# hp16555_adapter.net
KiCad netlist of a schematic drawn in EAGLE
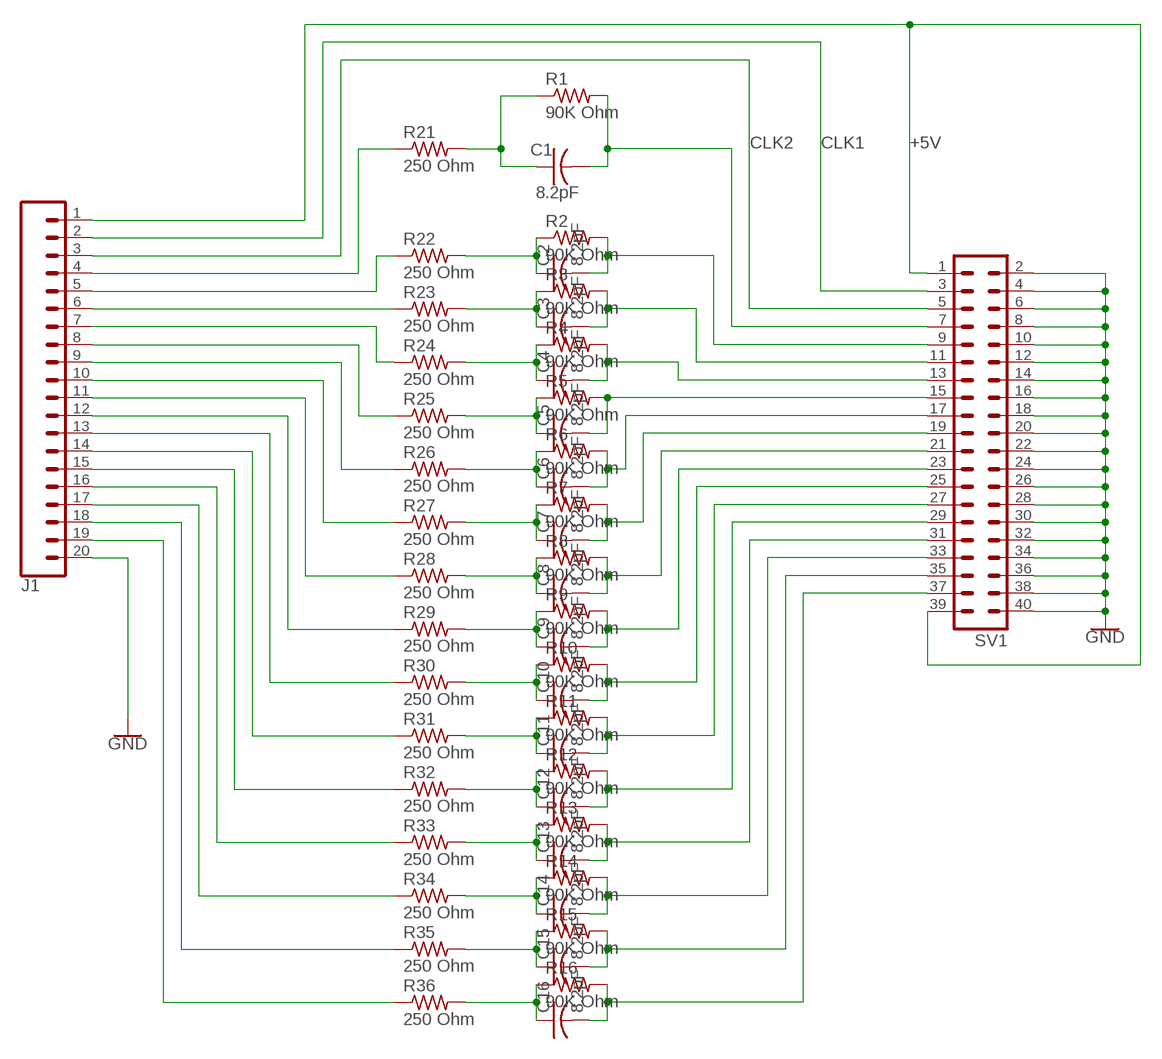
[diagram p0: schematic, sheet 1]

(export (version "E")
  (design (tool "Eeschema 10.0.6"))
  (components
    (comp (ref "C1")
      (value "8.2pF")
      (footprint "eagle-import:C1206")
      (libsource (lib "eagle-import") (part "C-USC1206"))
    )
    (comp (ref "C2")
      (value "8.2pF")
      (footprint "eagle-import:C1206")
      (libsource (lib "eagle-import") (part "C-USC1206"))
    )
    (comp (ref "C3")
      (value "8.2pF")
      (footprint "eagle-import:C1206")
      (libsource (lib "eagle-import") (part "C-USC1206"))
    )
    (comp (ref "C4")
      (value "8.2pF")
      (footprint "eagle-import:C1206")
      (libsource (lib "eagle-import") (part "C-USC1206"))
    )
    (comp (ref "C5")
      (value "8.2pF")
      (footprint "eagle-import:C1206")
      (libsource (lib "eagle-import") (part "C-USC1206"))
    )
    (comp (ref "C6")
      (value "8.2pF")
      (footprint "eagle-import:C1206")
      (libsource (lib "eagle-import") (part "C-USC1206"))
    )
    (comp (ref "C7")
      (value "8.2pF")
      (footprint "eagle-import:C1206")
      (libsource (lib "eagle-import") (part "C-USC1206"))
    )
    (comp (ref "C8")
      (value "8.2pF")
      (footprint "eagle-import:C1206")
      (libsource (lib "eagle-import") (part "C-USC1206"))
    )
    (comp (ref "C9")
      (value "8.2pF")
      (footprint "eagle-import:C1206")
      (libsource (lib "eagle-import") (part "C-USC1206"))
    )
    (comp (ref "C10")
      (value "8.2pF")
      (footprint "eagle-import:C1206")
      (libsource (lib "eagle-import") (part "C-USC1206"))
    )
    (comp (ref "C11")
      (value "8.2pF")
      (footprint "eagle-import:C1206")
      (libsource (lib "eagle-import") (part "C-USC1206"))
    )
    (comp (ref "C12")
      (value "8.2pF")
      (footprint "eagle-import:C1206")
      (libsource (lib "eagle-import") (part "C-USC1206"))
    )
    (comp (ref "C13")
      (value "8.2pF")
      (footprint "eagle-import:C1206")
      (libsource (lib "eagle-import") (part "C-USC1206"))
    )
    (comp (ref "C14")
      (value "8.2pF")
      (footprint "eagle-import:C1206")
      (libsource (lib "eagle-import") (part "C-USC1206"))
    )
    (comp (ref "C15")
      (value "8.2pF")
      (footprint "eagle-import:C1206")
      (libsource (lib "eagle-import") (part "C-USC1206"))
    )
    (comp (ref "C16")
      (value "8.2pF")
      (footprint "eagle-import:C1206")
      (libsource (lib "eagle-import") (part "C-USC1206"))
    )
    (comp (ref "J1")
      (value "CONN_20")
      (footprint "eagle-import:1X20")
      (libsource (lib "eagle-import") (part "CONN_20"))
    )
    (comp (ref "R1")
      (value "90K Ohm")
      (footprint "eagle-import:M1206")
      (libsource (lib "eagle-import") (part "R-US_M1206"))
    )
    (comp (ref "R2")
      (value "90K Ohm")
      (footprint "eagle-import:M1206")
      (libsource (lib "eagle-import") (part "R-US_M1206"))
    )
    (comp (ref "R3")
      (value "90K Ohm")
      (footprint "eagle-import:M1206")
      (libsource (lib "eagle-import") (part "R-US_M1206"))
    )
    (comp (ref "R4")
      (value "90K Ohm")
      (footprint "eagle-import:M1206")
      (libsource (lib "eagle-import") (part "R-US_M1206"))
    )
    (comp (ref "R5")
      (value "90K Ohm")
      (footprint "eagle-import:M1206")
      (libsource (lib "eagle-import") (part "R-US_M1206"))
    )
    (comp (ref "R6")
      (value "90K Ohm")
      (footprint "eagle-import:M1206")
      (libsource (lib "eagle-import") (part "R-US_M1206"))
    )
    (comp (ref "R7")
      (value "90K Ohm")
      (footprint "eagle-import:M1206")
      (libsource (lib "eagle-import") (part "R-US_M1206"))
    )
    (comp (ref "R8")
      (value "90K Ohm")
      (footprint "eagle-import:M1206")
      (libsource (lib "eagle-import") (part "R-US_M1206"))
    )
    (comp (ref "R9")
      (value "90K Ohm")
      (footprint "eagle-import:M1206")
      (libsource (lib "eagle-import") (part "R-US_M1206"))
    )
    (comp (ref "R10")
      (value "90K Ohm")
      (footprint "eagle-import:M1206")
      (libsource (lib "eagle-import") (part "R-US_M1206"))
    )
    (comp (ref "R11")
      (value "90K Ohm")
      (footprint "eagle-import:M1206")
      (libsource (lib "eagle-import") (part "R-US_M1206"))
    )
    (comp (ref "R12")
      (value "90K Ohm")
      (footprint "eagle-import:M1206")
      (libsource (lib "eagle-import") (part "R-US_M1206"))
    )
    (comp (ref "R13")
      (value "90K Ohm")
      (footprint "eagle-import:M1206")
      (libsource (lib "eagle-import") (part "R-US_M1206"))
    )
    (comp (ref "R14")
      (value "90K Ohm")
      (footprint "eagle-import:M1206")
      (libsource (lib "eagle-import") (part "R-US_M1206"))
    )
    (comp (ref "R15")
      (value "90K Ohm")
      (footprint "eagle-import:M1206")
      (libsource (lib "eagle-import") (part "R-US_M1206"))
    )
    (comp (ref "R16")
      (value "90K Ohm")
      (footprint "eagle-import:M1206")
      (libsource (lib "eagle-import") (part "R-US_M1206"))
    )
    (comp (ref "R21")
      (value "250 Ohm")
      (footprint "eagle-import:M1206")
      (libsource (lib "eagle-import") (part "R-US_M1206"))
    )
    (comp (ref "R22")
      (value "250 Ohm")
      (footprint "eagle-import:M1206")
      (libsource (lib "eagle-import") (part "R-US_M1206"))
    )
    (comp (ref "R23")
      (value "250 Ohm")
      (footprint "eagle-import:M1206")
      (libsource (lib "eagle-import") (part "R-US_M1206"))
    )
    (comp (ref "R24")
      (value "250 Ohm")
      (footprint "eagle-import:M1206")
      (libsource (lib "eagle-import") (part "R-US_M1206"))
    )
    (comp (ref "R25")
      (value "250 Ohm")
      (footprint "eagle-import:M1206")
      (libsource (lib "eagle-import") (part "R-US_M1206"))
    )
    (comp (ref "R26")
      (value "250 Ohm")
      (footprint "eagle-import:M1206")
      (libsource (lib "eagle-import") (part "R-US_M1206"))
    )
    (comp (ref "R27")
      (value "250 Ohm")
      (footprint "eagle-import:M1206")
      (libsource (lib "eagle-import") (part "R-US_M1206"))
    )
    (comp (ref "R28")
      (value "250 Ohm")
      (footprint "eagle-import:M1206")
      (libsource (lib "eagle-import") (part "R-US_M1206"))
    )
    (comp (ref "R29")
      (value "250 Ohm")
      (footprint "eagle-import:M1206")
      (libsource (lib "eagle-import") (part "R-US_M1206"))
    )
    (comp (ref "R30")
      (value "250 Ohm")
      (footprint "eagle-import:M1206")
      (libsource (lib "eagle-import") (part "R-US_M1206"))
    )
    (comp (ref "R31")
      (value "250 Ohm")
      (footprint "eagle-import:M1206")
      (libsource (lib "eagle-import") (part "R-US_M1206"))
    )
    (comp (ref "R32")
      (value "250 Ohm")
      (footprint "eagle-import:M1206")
      (libsource (lib "eagle-import") (part "R-US_M1206"))
    )
    (comp (ref "R33")
      (value "250 Ohm")
      (footprint "eagle-import:M1206")
      (libsource (lib "eagle-import") (part "R-US_M1206"))
    )
    (comp (ref "R34")
      (value "250 Ohm")
      (footprint "eagle-import:M1206")
      (libsource (lib "eagle-import") (part "R-US_M1206"))
    )
    (comp (ref "R35")
      (value "250 Ohm")
      (footprint "eagle-import:M1206")
      (libsource (lib "eagle-import") (part "R-US_M1206"))
    )
    (comp (ref "R36")
      (value "250 Ohm")
      (footprint "eagle-import:M1206")
      (libsource (lib "eagle-import") (part "R-US_M1206"))
    )
    (comp (ref "SV1")
      (value "MA20-2")
      (footprint "eagle-import:MA20-2")
      (libsource (lib "eagle-import") (part "MA20-2"))
    )
  )
  (nets
    (net (code "1") (name "/+5V") (class "Default")
      (node (ref "J1") (pin "1") (pinfunction "1_1") (pintype "passive"))
      (node (ref "SV1") (pin "1") (pinfunction "1_1") (pintype "passive"))
      (node (ref "SV1") (pin "39") (pinfunction "39_39") (pintype "passive"))
    )
    (net (code "2") (name "/CLK1") (class "Default")
      (node (ref "J1") (pin "2") (pinfunction "2_2") (pintype "passive"))
      (node (ref "SV1") (pin "3") (pinfunction "3_3") (pintype "passive"))
    )
    (net (code "3") (name "/CLK2") (class "Default")
      (node (ref "J1") (pin "3") (pinfunction "3_3") (pintype "passive"))
      (node (ref "SV1") (pin "5") (pinfunction "5_5") (pintype "passive"))
    )
    (net (code "4") (name "GND") (class "Default")
      (node (ref "J1") (pin "20") (pinfunction "20_20") (pintype "passive"))
      (node (ref "SV1") (pin "10") (pinfunction "10_10") (pintype "passive"))
      (node (ref "SV1") (pin "12") (pinfunction "12_12") (pintype "passive"))
      (node (ref "SV1") (pin "14") (pinfunction "14_14") (pintype "passive"))
      (node (ref "SV1") (pin "16") (pinfunction "16_16") (pintype "passive"))
      (node (ref "SV1") (pin "18") (pinfunction "18_18") (pintype "passive"))
      (node (ref "SV1") (pin "2") (pinfunction "2_2") (pintype "passive"))
      (node (ref "SV1") (pin "20") (pinfunction "20_20") (pintype "passive"))
      (node (ref "SV1") (pin "22") (pinfunction "22_22") (pintype "passive"))
      (node (ref "SV1") (pin "24") (pinfunction "24_24") (pintype "passive"))
      (node (ref "SV1") (pin "26") (pinfunction "26_26") (pintype "passive"))
      (node (ref "SV1") (pin "28") (pinfunction "28_28") (pintype "passive"))
      (node (ref "SV1") (pin "30") (pinfunction "30_30") (pintype "passive"))
      (node (ref "SV1") (pin "32") (pinfunction "32_32") (pintype "passive"))
      (node (ref "SV1") (pin "34") (pinfunction "34_34") (pintype "passive"))
      (node (ref "SV1") (pin "36") (pinfunction "36_36") (pintype "passive"))
      (node (ref "SV1") (pin "38") (pinfunction "38_38") (pintype "passive"))
      (node (ref "SV1") (pin "4") (pinfunction "4_4") (pintype "passive"))
      (node (ref "SV1") (pin "40") (pinfunction "40_40") (pintype "passive"))
      (node (ref "SV1") (pin "6") (pinfunction "6_6") (pintype "passive"))
      (node (ref "SV1") (pin "8") (pinfunction "8_8") (pintype "passive"))
    )
    (net (code "5") (name "Net-(C1-Pad1)") (class "Default")
      (node (ref "C1") (pin "1") (pinfunction "1_1") (pintype "passive"))
      (node (ref "R1") (pin "1") (pinfunction "1_1") (pintype "passive"))
      (node (ref "R21") (pin "2") (pinfunction "2_2") (pintype "passive"))
    )
    (net (code "6") (name "Net-(C1-Pad2)") (class "Default")
      (node (ref "C1") (pin "2") (pinfunction "2_2") (pintype "passive"))
      (node (ref "R1") (pin "2") (pinfunction "2_2") (pintype "passive"))
      (node (ref "SV1") (pin "7") (pinfunction "7_7") (pintype "passive"))
    )
    (net (code "7") (name "Net-(C2-Pad1)") (class "Default")
      (node (ref "C2") (pin "1") (pinfunction "1_1") (pintype "passive"))
      (node (ref "R2") (pin "1") (pinfunction "1_1") (pintype "passive"))
      (node (ref "R22") (pin "2") (pinfunction "2_2") (pintype "passive"))
    )
    (net (code "8") (name "Net-(C2-Pad2)") (class "Default")
      (node (ref "C2") (pin "2") (pinfunction "2_2") (pintype "passive"))
      (node (ref "R2") (pin "2") (pinfunction "2_2") (pintype "passive"))
      (node (ref "SV1") (pin "9") (pinfunction "9_9") (pintype "passive"))
    )
    (net (code "9") (name "Net-(C3-Pad1)") (class "Default")
      (node (ref "C3") (pin "1") (pinfunction "1_1") (pintype "passive"))
      (node (ref "R23") (pin "2") (pinfunction "2_2") (pintype "passive"))
      (node (ref "R3") (pin "1") (pinfunction "1_1") (pintype "passive"))
    )
    (net (code "10") (name "Net-(C3-Pad2)") (class "Default")
      (node (ref "C3") (pin "2") (pinfunction "2_2") (pintype "passive"))
      (node (ref "R3") (pin "2") (pinfunction "2_2") (pintype "passive"))
      (node (ref "SV1") (pin "11") (pinfunction "11_11") (pintype "passive"))
    )
    (net (code "11") (name "Net-(C4-Pad1)") (class "Default")
      (node (ref "C4") (pin "1") (pinfunction "1_1") (pintype "passive"))
      (node (ref "R24") (pin "2") (pinfunction "2_2") (pintype "passive"))
      (node (ref "R4") (pin "1") (pinfunction "1_1") (pintype "passive"))
    )
    (net (code "12") (name "Net-(C4-Pad2)") (class "Default")
      (node (ref "C4") (pin "2") (pinfunction "2_2") (pintype "passive"))
      (node (ref "R4") (pin "2") (pinfunction "2_2") (pintype "passive"))
      (node (ref "SV1") (pin "13") (pinfunction "13_13") (pintype "passive"))
    )
    (net (code "13") (name "Net-(C5-Pad1)") (class "Default")
      (node (ref "C5") (pin "1") (pinfunction "1_1") (pintype "passive"))
      (node (ref "R25") (pin "2") (pinfunction "2_2") (pintype "passive"))
      (node (ref "R5") (pin "1") (pinfunction "1_1") (pintype "passive"))
    )
    (net (code "14") (name "Net-(C5-Pad2)") (class "Default")
      (node (ref "C5") (pin "2") (pinfunction "2_2") (pintype "passive"))
      (node (ref "R5") (pin "2") (pinfunction "2_2") (pintype "passive"))
      (node (ref "SV1") (pin "15") (pinfunction "15_15") (pintype "passive"))
    )
    (net (code "15") (name "Net-(C6-Pad1)") (class "Default")
      (node (ref "C6") (pin "1") (pinfunction "1_1") (pintype "passive"))
      (node (ref "R26") (pin "2") (pinfunction "2_2") (pintype "passive"))
      (node (ref "R6") (pin "1") (pinfunction "1_1") (pintype "passive"))
    )
    (net (code "16") (name "Net-(C6-Pad2)") (class "Default")
      (node (ref "C6") (pin "2") (pinfunction "2_2") (pintype "passive"))
      (node (ref "R6") (pin "2") (pinfunction "2_2") (pintype "passive"))
      (node (ref "SV1") (pin "17") (pinfunction "17_17") (pintype "passive"))
    )
    (net (code "17") (name "Net-(C7-Pad1)") (class "Default")
      (node (ref "C7") (pin "1") (pinfunction "1_1") (pintype "passive"))
      (node (ref "R27") (pin "2") (pinfunction "2_2") (pintype "passive"))
      (node (ref "R7") (pin "1") (pinfunction "1_1") (pintype "passive"))
    )
    (net (code "18") (name "Net-(C7-Pad2)") (class "Default")
      (node (ref "C7") (pin "2") (pinfunction "2_2") (pintype "passive"))
      (node (ref "R7") (pin "2") (pinfunction "2_2") (pintype "passive"))
      (node (ref "SV1") (pin "19") (pinfunction "19_19") (pintype "passive"))
    )
    (net (code "19") (name "Net-(C8-Pad1)") (class "Default")
      (node (ref "C8") (pin "1") (pinfunction "1_1") (pintype "passive"))
      (node (ref "R28") (pin "2") (pinfunction "2_2") (pintype "passive"))
      (node (ref "R8") (pin "1") (pinfunction "1_1") (pintype "passive"))
    )
    (net (code "20") (name "Net-(C8-Pad2)") (class "Default")
      (node (ref "C8") (pin "2") (pinfunction "2_2") (pintype "passive"))
      (node (ref "R8") (pin "2") (pinfunction "2_2") (pintype "passive"))
      (node (ref "SV1") (pin "21") (pinfunction "21_21") (pintype "passive"))
    )
    (net (code "21") (name "Net-(C9-Pad1)") (class "Default")
      (node (ref "C9") (pin "1") (pinfunction "1_1") (pintype "passive"))
      (node (ref "R29") (pin "2") (pinfunction "2_2") (pintype "passive"))
      (node (ref "R9") (pin "1") (pinfunction "1_1") (pintype "passive"))
    )
    (net (code "22") (name "Net-(C9-Pad2)") (class "Default")
      (node (ref "C9") (pin "2") (pinfunction "2_2") (pintype "passive"))
      (node (ref "R9") (pin "2") (pinfunction "2_2") (pintype "passive"))
      (node (ref "SV1") (pin "23") (pinfunction "23_23") (pintype "passive"))
    )
    (net (code "23") (name "Net-(C10-Pad1)") (class "Default")
      (node (ref "C10") (pin "1") (pinfunction "1_1") (pintype "passive"))
      (node (ref "R10") (pin "1") (pinfunction "1_1") (pintype "passive"))
      (node (ref "R30") (pin "2") (pinfunction "2_2") (pintype "passive"))
    )
    (net (code "24") (name "Net-(C10-Pad2)") (class "Default")
      (node (ref "C10") (pin "2") (pinfunction "2_2") (pintype "passive"))
      (node (ref "R10") (pin "2") (pinfunction "2_2") (pintype "passive"))
      (node (ref "SV1") (pin "25") (pinfunction "25_25") (pintype "passive"))
    )
    (net (code "25") (name "Net-(C11-Pad1)") (class "Default")
      (node (ref "C11") (pin "1") (pinfunction "1_1") (pintype "passive"))
      (node (ref "R11") (pin "1") (pinfunction "1_1") (pintype "passive"))
      (node (ref "R31") (pin "2") (pinfunction "2_2") (pintype "passive"))
    )
    (net (code "26") (name "Net-(C11-Pad2)") (class "Default")
      (node (ref "C11") (pin "2") (pinfunction "2_2") (pintype "passive"))
      (node (ref "R11") (pin "2") (pinfunction "2_2") (pintype "passive"))
      (node (ref "SV1") (pin "27") (pinfunction "27_27") (pintype "passive"))
    )
    (net (code "27") (name "Net-(C12-Pad1)") (class "Default")
      (node (ref "C12") (pin "1") (pinfunction "1_1") (pintype "passive"))
      (node (ref "R12") (pin "1") (pinfunction "1_1") (pintype "passive"))
      (node (ref "R32") (pin "2") (pinfunction "2_2") (pintype "passive"))
    )
    (net (code "28") (name "Net-(C12-Pad2)") (class "Default")
      (node (ref "C12") (pin "2") (pinfunction "2_2") (pintype "passive"))
      (node (ref "R12") (pin "2") (pinfunction "2_2") (pintype "passive"))
      (node (ref "SV1") (pin "29") (pinfunction "29_29") (pintype "passive"))
    )
    (net (code "29") (name "Net-(C13-Pad1)") (class "Default")
      (node (ref "C13") (pin "1") (pinfunction "1_1") (pintype "passive"))
      (node (ref "R13") (pin "1") (pinfunction "1_1") (pintype "passive"))
      (node (ref "R33") (pin "2") (pinfunction "2_2") (pintype "passive"))
    )
    (net (code "30") (name "Net-(C13-Pad2)") (class "Default")
      (node (ref "C13") (pin "2") (pinfunction "2_2") (pintype "passive"))
      (node (ref "R13") (pin "2") (pinfunction "2_2") (pintype "passive"))
      (node (ref "SV1") (pin "31") (pinfunction "31_31") (pintype "passive"))
    )
    (net (code "31") (name "Net-(C14-Pad1)") (class "Default")
      (node (ref "C14") (pin "1") (pinfunction "1_1") (pintype "passive"))
      (node (ref "R14") (pin "1") (pinfunction "1_1") (pintype "passive"))
      (node (ref "R34") (pin "2") (pinfunction "2_2") (pintype "passive"))
    )
    (net (code "32") (name "Net-(C14-Pad2)") (class "Default")
      (node (ref "C14") (pin "2") (pinfunction "2_2") (pintype "passive"))
      (node (ref "R14") (pin "2") (pinfunction "2_2") (pintype "passive"))
      (node (ref "SV1") (pin "33") (pinfunction "33_33") (pintype "passive"))
    )
    (net (code "33") (name "Net-(C15-Pad1)") (class "Default")
      (node (ref "C15") (pin "1") (pinfunction "1_1") (pintype "passive"))
      (node (ref "R15") (pin "1") (pinfunction "1_1") (pintype "passive"))
      (node (ref "R35") (pin "2") (pinfunction "2_2") (pintype "passive"))
    )
    (net (code "34") (name "Net-(C15-Pad2)") (class "Default")
      (node (ref "C15") (pin "2") (pinfunction "2_2") (pintype "passive"))
      (node (ref "R15") (pin "2") (pinfunction "2_2") (pintype "passive"))
      (node (ref "SV1") (pin "35") (pinfunction "35_35") (pintype "passive"))
    )
    (net (code "35") (name "Net-(C16-Pad1)") (class "Default")
      (node (ref "C16") (pin "1") (pinfunction "1_1") (pintype "passive"))
      (node (ref "R16") (pin "1") (pinfunction "1_1") (pintype "passive"))
      (node (ref "R36") (pin "2") (pinfunction "2_2") (pintype "passive"))
    )
    (net (code "36") (name "Net-(C16-Pad2)") (class "Default")
      (node (ref "C16") (pin "2") (pinfunction "2_2") (pintype "passive"))
      (node (ref "R16") (pin "2") (pinfunction "2_2") (pintype "passive"))
      (node (ref "SV1") (pin "37") (pinfunction "37_37") (pintype "passive"))
    )
    (net (code "37") (name "Net-(J1-Pad4)") (class "Default")
      (node (ref "J1") (pin "4") (pinfunction "4_4") (pintype "passive"))
      (node (ref "R21") (pin "1") (pinfunction "1_1") (pintype "passive"))
    )
    (net (code "38") (name "Net-(J1-Pad5)") (class "Default")
      (node (ref "J1") (pin "5") (pinfunction "5_5") (pintype "passive"))
      (node (ref "R22") (pin "1") (pinfunction "1_1") (pintype "passive"))
    )
    (net (code "39") (name "Net-(J1-Pad6)") (class "Default")
      (node (ref "J1") (pin "6") (pinfunction "6_6") (pintype "passive"))
      (node (ref "R23") (pin "1") (pinfunction "1_1") (pintype "passive"))
    )
    (net (code "40") (name "Net-(J1-Pad7)") (class "Default")
      (node (ref "J1") (pin "7") (pinfunction "7_7") (pintype "passive"))
      (node (ref "R24") (pin "1") (pinfunction "1_1") (pintype "passive"))
    )
    (net (code "41") (name "Net-(J1-Pad8)") (class "Default")
      (node (ref "J1") (pin "8") (pinfunction "8_8") (pintype "passive"))
      (node (ref "R25") (pin "1") (pinfunction "1_1") (pintype "passive"))
    )
    (net (code "42") (name "Net-(J1-Pad9)") (class "Default")
      (node (ref "J1") (pin "9") (pinfunction "9_9") (pintype "passive"))
      (node (ref "R26") (pin "1") (pinfunction "1_1") (pintype "passive"))
    )
    (net (code "43") (name "Net-(J1-Pad10)") (class "Default")
      (node (ref "J1") (pin "10") (pinfunction "10_10") (pintype "passive"))
      (node (ref "R27") (pin "1") (pinfunction "1_1") (pintype "passive"))
    )
    (net (code "44") (name "Net-(J1-Pad11)") (class "Default")
      (node (ref "J1") (pin "11") (pinfunction "11_11") (pintype "passive"))
      (node (ref "R28") (pin "1") (pinfunction "1_1") (pintype "passive"))
    )
    (net (code "45") (name "Net-(J1-Pad12)") (class "Default")
      (node (ref "J1") (pin "12") (pinfunction "12_12") (pintype "passive"))
      (node (ref "R29") (pin "1") (pinfunction "1_1") (pintype "passive"))
    )
    (net (code "46") (name "Net-(J1-Pad13)") (class "Default")
      (node (ref "J1") (pin "13") (pinfunction "13_13") (pintype "passive"))
      (node (ref "R30") (pin "1") (pinfunction "1_1") (pintype "passive"))
    )
    (net (code "47") (name "Net-(J1-Pad14)") (class "Default")
      (node (ref "J1") (pin "14") (pinfunction "14_14") (pintype "passive"))
      (node (ref "R31") (pin "1") (pinfunction "1_1") (pintype "passive"))
    )
    (net (code "48") (name "Net-(J1-Pad15)") (class "Default")
      (node (ref "J1") (pin "15") (pinfunction "15_15") (pintype "passive"))
      (node (ref "R32") (pin "1") (pinfunction "1_1") (pintype "passive"))
    )
    (net (code "49") (name "Net-(J1-Pad16)") (class "Default")
      (node (ref "J1") (pin "16") (pinfunction "16_16") (pintype "passive"))
      (node (ref "R33") (pin "1") (pinfunction "1_1") (pintype "passive"))
    )
    (net (code "50") (name "Net-(J1-Pad17)") (class "Default")
      (node (ref "J1") (pin "17") (pinfunction "17_17") (pintype "passive"))
      (node (ref "R34") (pin "1") (pinfunction "1_1") (pintype "passive"))
    )
    (net (code "51") (name "Net-(J1-Pad18)") (class "Default")
      (node (ref "J1") (pin "18") (pinfunction "18_18") (pintype "passive"))
      (node (ref "R35") (pin "1") (pinfunction "1_1") (pintype "passive"))
    )
    (net (code "52") (name "Net-(J1-Pad19)") (class "Default")
      (node (ref "J1") (pin "19") (pinfunction "19_19") (pintype "passive"))
      (node (ref "R36") (pin "1") (pinfunction "1_1") (pintype "passive"))
    )
  )
)
